# 24V_Converter.net
KiCad netlist of a schematic drawn in Altium Designer
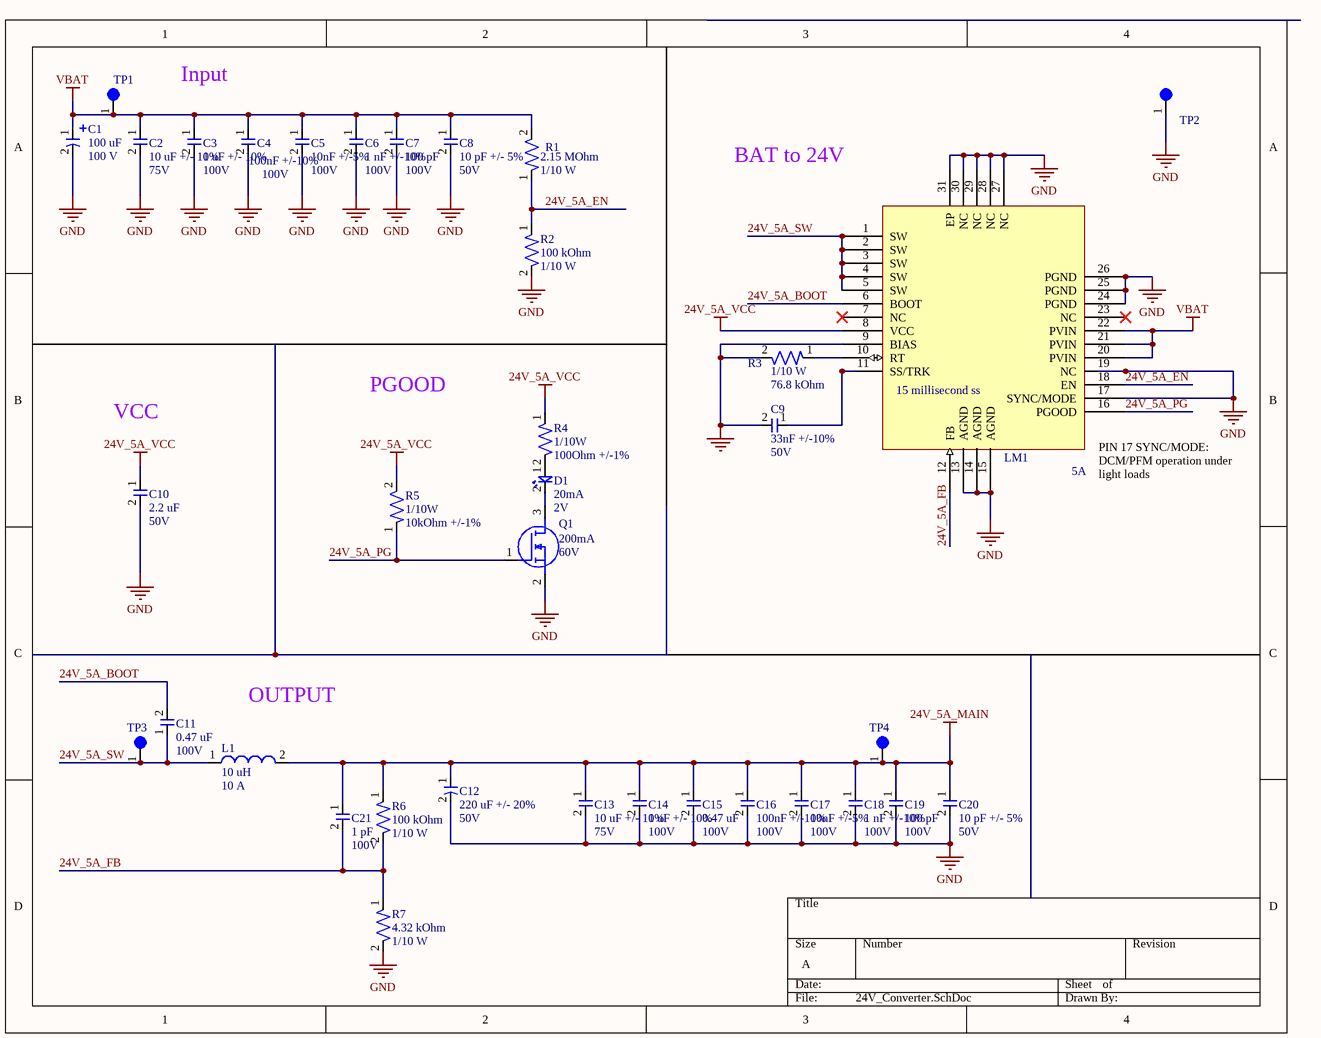
[diagram p0: 24V_Converter.SchDoc]

(export (version "E")
  (design (tool "Eeschema 10.0.6"))
  (components
    (comp (ref "C1")
      (value "100SEV100M12.5X16")
      (footprint "ELEC-100U-0001")
      (description "100 µF 100 V Aluminum Electrolytic Capacitors Radial, Can - SMD 2000 Hrs @ 85°C")
      (fields
        (field (name "MANUFACTURER") "Rubycon")
        (field (name "TOLERANCE") "+/- 20%")
        (field (name "CAPACITANCE") "100 uF")
        (field (name "VOLTAGE") "100 V")
      )
      (libsource (lib "MasterLib") (part "ELEC-100U-0001"))
    )
    (comp (ref "C2")
      (value "C3225X7R1N106K250AC")
      (footprint "CAP-1210")
      (description "10 µF ±10% 75V Ceramic Capacitor X7R 1210 (3225 Metric)")
      (fields (field (name "CAPACITANCE") "10 uF +/- 10%") (field (name "VOLTAGE RATING") "75V"))
      (libsource (lib "MasterLib") (part "CAP-10U-0004"))
    )
    (comp (ref "C3")
      (value "CL31B105KCHNNNE")
      (footprint "CAP-1206 - duplicate")
      (description "1 µF ±10% 100V Ceramic Capacitor X7R 1206 (3216 Metric)")
      (fields (field (name "CAPACITANCE") "1 uF +/- 10%") (field (name "VOLTAGE") "100V"))
      (libsource (lib "MasterLib") (part "CAP-1U-0001"))
    )
    (comp (ref "C4")
      (value "CC0603KRX7R0BB104")
      (footprint "CAP-0603")
      (description "CAP CER 0.1UF 100V X7R 0603")
      (fields
        (field (name "MANUFACTURER") "YAGEO")
        (field (name "CAPACITANCE") "100nF +/-10%")
        (field (name "VOLTAGE RATING") "100V")
      )
      (libsource (lib "MasterLib") (part "CAP-100N-0001"))
    )
    (comp (ref "C5")
      (value "C1608C0G2A103J080AC")
      (footprint "CAP-0603")
      (description "CAP CER 10000PF 100V C0G 0603")
      (fields
        (field (name "MANUFACTURER") "TDK Corporation")
        (field (name "CAPACITANCE") "10nF +/-5%")
        (field (name "VOLTAGE RATING") "100V")
      )
      (libsource (lib "MasterLib") (part "CAP-10N-0002"))
    )
    (comp (ref "C6")
      (value "C0603Y102K1RAC7867")
      (footprint "CAP-0603")
      (description "1000 pF ±10% 100V Ceramic Capacitor X7R 0603 (1608 Metric)")
      (fields (field (name "CAPACITANCE") "1 nF +/-10%") (field (name "VOLTAGE") "100V"))
      (libsource (lib "MasterLib") (part "CAP-1N-0001"))
    )
    (comp (ref "C7")
      (value "0603N101J101CT")
      (footprint "CAP-0603")
      (description "100 pF ±5% 100V Ceramic Capacitor C0G, NP0 0603 (1608 Metric)")
      (fields
        (field (name "TOLERANCE") "+/-5%")
        (field (name "CAPACITANCE") "100 pF")
        (field (name "VOLTAGE") "100V")
      )
      (libsource (lib "MasterLib") (part "CAP-100P-0002"))
    )
    (comp (ref "C8")
      (value "0603N100J500CT")
      (footprint "CAP-0603")
      (description "10 pF ±5% 50V Ceramic Capacitor C0G, NP0 0603 (1608 Metric)")
      (fields
        (field (name "MANUFACTURER") "Walshin Technology Corporation")
        (field (name "CAPACITANCE") "10 pF +/- 5%")
        (field (name "VOLTAGE RATING") "50V")
      )
      (libsource (lib "MasterLib") (part "CAP-10P-0001"))
    )
    (comp (ref "C9")
      (value "CC0603KRX7R9BB333")
      (footprint "CAP-0603")
      (description "0.033 µF ±10% 50V Ceramic Capacitor X7R 0603 (1608 Metric)")
      (fields
        (field (name "MANUFACTURER") "YAGEO")
        (field (name "CAPACITANCE") "33nF +/-10%")
        (field (name "VOLTAGE RATING") "50V")
      )
      (libsource (lib "MasterLib") (part "CAP-33N-0001"))
    )
    (comp (ref "C10")
      (value "UMK107BBJ225KA-T")
      (footprint "CAP-0603")
      (description "2.2 µF ±10% 50V Ceramic Capacitor X5R 0603 (1608 Metric)")
      (fields (field (name "CAPACITANCE") "2.2 uF") (field (name "OLTAGE") "50V"))
      (libsource (lib "MasterLib") (part "CAP-2.2U-0001"))
    )
    (comp (ref "C11")
      (value "KAM21KR72A474KL")
      (footprint "CAP-0805")
      (description "0.47 µF ±10% 100V Ceramic Capacitor X7R 0805 (2012 Metric)")
      (fields
        (field (name "TOLERANCE") "+/- 10%")
        (field (name "CAPACITANCE") "0.47 uF")
        (field (name "VOLTAGE") "100V")
      )
      (libsource (lib "MasterLib") (part "CAP-0.47U-0001"))
    )
    (comp (ref "C12")
      (value "50TZV220M10X10.5")
      (footprint "ELEC-220U-0003")
      (description "220 µF 50 V Aluminum Electrolytic Capacitors Radial, Can - SMD 2000 Hrs @ 105°C")
      (fields (field (name "CAPACITANCE") "220 uF +/- 20%") (field (name "VOLTAGE RATING") "50V"))
      (libsource (lib "MasterLib") (part "ELEC-220U-0003"))
    )
    (comp (ref "C13")
      (value "C3225X7R1N106K250AC")
      (footprint "CAP-1210")
      (description "10 µF ±10% 75V Ceramic Capacitor X7R 1210 (3225 Metric)")
      (fields (field (name "CAPACITANCE") "10 uF +/- 10%") (field (name "VOLTAGE RATING") "75V"))
      (libsource (lib "MasterLib") (part "CAP-10U-0004"))
    )
    (comp (ref "C14")
      (value "CL31B105KCHNNNE")
      (footprint "CAP-1206 - duplicate")
      (description "1 µF ±10% 100V Ceramic Capacitor X7R 1206 (3216 Metric)")
      (fields (field (name "CAPACITANCE") "1 uF +/- 10%") (field (name "VOLTAGE") "100V"))
      (libsource (lib "MasterLib") (part "CAP-1U-0001"))
    )
    (comp (ref "C15")
      (value "KAM21KR72A474KL")
      (footprint "CAP-0805")
      (description "0.47 µF ±10% 100V Ceramic Capacitor X7R 0805 (2012 Metric)")
      (fields
        (field (name "TOLERANCE") "+/- 10%")
        (field (name "CAPACITANCE") "0.47 uF")
        (field (name "VOLTAGE") "100V")
      )
      (libsource (lib "MasterLib") (part "CAP-0.47U-0001"))
    )
    (comp (ref "C16")
      (value "CC0603KRX7R0BB104")
      (footprint "CAP-0603")
      (description "CAP CER 0.1UF 100V X7R 0603")
      (fields
        (field (name "MANUFACTURER") "YAGEO")
        (field (name "CAPACITANCE") "100nF +/-10%")
        (field (name "VOLTAGE RATING") "100V")
      )
      (libsource (lib "MasterLib") (part "CAP-100N-0001"))
    )
    (comp (ref "C17")
      (value "C1608C0G2A103J080AC")
      (footprint "CAP-0603")
      (description "CAP CER 10000PF 100V C0G 0603")
      (fields
        (field (name "MANUFACTURER") "TDK Corporation")
        (field (name "CAPACITANCE") "10nF +/-5%")
        (field (name "VOLTAGE RATING") "100V")
      )
      (libsource (lib "MasterLib") (part "CAP-10N-0002"))
    )
    (comp (ref "C18")
      (value "C0603Y102K1RAC7867")
      (footprint "CAP-0603")
      (description "1000 pF ±10% 100V Ceramic Capacitor X7R 0603 (1608 Metric)")
      (fields (field (name "CAPACITANCE") "1 nF +/-10%") (field (name "VOLTAGE") "100V"))
      (libsource (lib "MasterLib") (part "CAP-1N-0001"))
    )
    (comp (ref "C19")
      (value "0603N101J101CT")
      (footprint "CAP-0603")
      (description "100 pF ±5% 100V Ceramic Capacitor C0G, NP0 0603 (1608 Metric)")
      (fields
        (field (name "TOLERANCE") "+/-5%")
        (field (name "CAPACITANCE") "100 pF")
        (field (name "VOLTAGE") "100V")
      )
      (libsource (lib "MasterLib") (part "CAP-100P-0002"))
    )
    (comp (ref "C20")
      (value "0603N100J500CT")
      (footprint "CAP-0603")
      (description "10 pF ±5% 50V Ceramic Capacitor C0G, NP0 0603 (1608 Metric)")
      (fields
        (field (name "MANUFACTURER") "Walshin Technology Corporation")
        (field (name "CAPACITANCE") "10 pF +/- 5%")
        (field (name "VOLTAGE RATING") "50V")
      )
      (libsource (lib "MasterLib") (part "CAP-10P-0001"))
    )
    (comp (ref "C21")
      (value "885012006087")
      (footprint "CAP-0603")
      (description "1 pF ±0.25pF 100V Ceramic Capacitor C0G, NP0 0603 (1608 Metric)")
      (fields
        (field (name "TOLERANCE") "+/- 0.25 pF")
        (field (name "CAPACITANCE") "1 pF")
        (field (name "VOLTAGE") "100V")
      )
      (libsource (lib "MasterLib") (part "CAP-1P-0001"))
    )
    (comp (ref "D1")
      (value "150060AS75000")
      (footprint "LED-0603")
      (description "CAP CER 0.1UF 100V X7R 0603")
      (fields
        (field (name "MANUFACTURER") "Wurth Electronik")
        (field (name "CURRENT RATING") "20mA")
        (field (name "VF") "2V")
      )
      (libsource (lib "MasterLib") (part "LED_Amber_0001"))
    )
    (comp (ref "L1")
      (value "SRP1270-100M")
      (footprint "PWRIND-10U-0002")
      (description "10 µH Shielded Drum Core, Wirewound Inductor 10 A 16.8mOhm Max Nonstandard")
      (fields
        (field (name "TOLERANCE") "+/- 20%")
        (field (name "INDUCTANCE") "10 uH")
        (field (name "DCI") "10 A")
      )
      (libsource (lib "MasterLib") (part "PWRIND-10U-0002"))
    )
    (comp (ref "LM1")
      (value "LM76005RNPR")
      (footprint "IC-30-WQFN(6x4)")
      (description "Buck Switching Regulator IC Positive Adjustable 1V 1 Output 5A 30-WFQFN Exposed Pad")
      (fields (field (name "MANUFACTURER") "Texas Instruments") (field (name "CURRENT") "5A"))
      (libsource (lib "MasterLib") (part "IC-BUCK-0006"))
    )
    (comp (ref "Q1")
      (value "T2N7002AK,LM")
      (footprint "NMOS-SOT23-3")
      (description "MOSFET N-CH 60V 200MA SOT23")
      (fields
        (field (name "MANUFACTURER") "Toshiba")
        (field (name "ID-CONTINUOUS") "200mA")
        (field (name "VDS-MAX") "60V")
      )
      (libsource (lib "MasterLib") (part "NMOS-200MA-0001"))
    )
    (comp (ref "R1")
      (value "RC0603FR-072M15L")
      (footprint "RES-0603")
      (description "2.15 MOhms ±1% 0.1W, 1/10W Chip Resistor 0603 (1608 Metric) Moisture Resistant Thick Film")
      (fields
        (field (name "TOLERANCE") "+/-1%")
        (field (name "RESISTANCE") "2.15 MOhm")
        (field (name "POWER") "1/10 W")
      )
      (libsource (lib "MasterLib") (part "RES-2.15M-0001"))
    )
    (comp (ref "R2")
      (value "RC0603FR-07100KL")
      (footprint "RES-0603")
      (description "100 kOhms ±1% 0.1W, 1/10W Chip Resistor 0603 (1608 Metric) Moisture Resistant Thick Film")
      (fields
        (field (name "TOLERANCE") "+/- 1%")
        (field (name "RESISTANCE") "100 kOhm")
        (field (name "POWER") "1/10 W")
      )
      (libsource (lib "MasterLib") (part "RES-100K-0003"))
    )
    (comp (ref "R3")
      (value "RC0603FR-0776K8L")
      (footprint "RES-0603")
      (description "76.8 kOhms ±1% 0.1W, 1/10W Chip Resistor 0603 (1608 Metric) Moisture Resistant Thick Film")
      (fields
        (field (name "MANUFACTURER") "Yageo")
        (field (name "TOLERANCE") "+/- 1%")
        (field (name "POWER") "1/10 W")
        (field (name "RESISTANCE") "76.8 kOhm")
      )
      (libsource (lib "MasterLib") (part "RES-76.8K-0001"))
    )
    (comp (ref "R4")
      (value "AC0603FR-10100RL")
      (footprint "RES-0603")
      (description "100 Ohms ±1% 0.1W, 1/10W Chip Resistor 0603 (1608 Metric) Automotive AEC-Q200 Thick Film")
      (fields
        (field (name "MANUFACTURER") "YAGEO")
        (field (name "POWER RATING") "1/10W")
        (field (name "RESISTANCE") "100Ohm +/-1%")
      )
      (libsource (lib "MasterLib") (part "RES-100-0002"))
    )
    (comp (ref "R5")
      (value "RC0603FR-0710KP")
      (footprint "RES-0603")
      (description "RES SMD 10K OHM 1% 1/10W 0603")
      (fields
        (field (name "MANUFACTURER") "YAGEO")
        (field (name "POWER RATING") "1/10W")
        (field (name "RESISTANCE") "10kOhm +/-1%")
      )
      (libsource (lib "MasterLib") (part "RES-10K-0002"))
    )
    (comp (ref "R6")
      (value "RC0603FR-07100KL")
      (footprint "RES-0603")
      (description "100 kOhms ±1% 0.1W, 1/10W Chip Resistor 0603 (1608 Metric) Moisture Resistant Thick Film")
      (fields
        (field (name "TOLERANCE") "+/- 1%")
        (field (name "RESISTANCE") "100 kOhm")
        (field (name "POWER") "1/10 W")
      )
      (libsource (lib "MasterLib") (part "RES-100K-0003"))
    )
    (comp (ref "R7")
      (value "RC0603FR-074K32L")
      (footprint "RES-0603")
      (description "4.32 kOhms ±1% 0.1W, 1/10W Chip Resistor 0603 (1608 Metric) Moisture Resistant Thick Film")
      (fields
        (field (name "TOLERANCE") "+/-1%")
        (field (name "RESISTANCE") "4.32 kOhm")
        (field (name "POWER") "1/10 W")
      )
      (libsource (lib "MasterLib") (part "RES-4.32K-0001"))
    )
    (comp (ref "TP1")
      (value "5003")
      (footprint "TEST-POINT-0001")
      (description "Oranange PC Test Point, Miniature Phoisphor Bronze Silver Plating Through Hole Mounting Type")
      (libsource (lib "MasterLib") (part "TEST-POINT-0001"))
    )
    (comp (ref "TP2")
      (value "5003")
      (footprint "TEST-POINT-0001")
      (description "Oranange PC Test Point, Miniature Phoisphor Bronze Silver Plating Through Hole Mounting Type")
      (libsource (lib "MasterLib") (part "TEST-POINT-0001"))
    )
    (comp (ref "TP3")
      (value "5003")
      (footprint "TEST-POINT-0001")
      (description "Oranange PC Test Point, Miniature Phoisphor Bronze Silver Plating Through Hole Mounting Type")
      (libsource (lib "MasterLib") (part "TEST-POINT-0001"))
    )
    (comp (ref "TP4")
      (value "5003")
      (footprint "TEST-POINT-0001")
      (description "Oranange PC Test Point, Miniature Phoisphor Bronze Silver Plating Through Hole Mounting Type")
      (libsource (lib "MasterLib") (part "TEST-POINT-0001"))
    )
  )
  (nets
    (net (code "1") (name "/24V_5A_BOOT") (class "Default")
      (node (ref "C11") (pin "2") (pinfunction "2_2") (pintype "passive"))
      (node (ref "LM1") (pin "6") (pinfunction "BOOT_6") (pintype "power_in"))
    )
    (net (code "2") (name "/24V_5A_EN") (class "Default")
      (node (ref "LM1") (pin "18") (pinfunction "EN_18") (pintype "power_in"))
      (node (ref "R1") (pin "1") (pinfunction "1_1") (pintype "passive"))
      (node (ref "R2") (pin "1") (pinfunction "1_1") (pintype "passive"))
    )
    (net (code "3") (name "/24V_5A_FB") (class "Default")
      (node (ref "C21") (pin "2") (pinfunction "2_2") (pintype "passive"))
      (node (ref "LM1") (pin "12") (pinfunction "FB_12") (pintype "input"))
      (node (ref "R6") (pin "2") (pinfunction "2_2") (pintype "passive"))
      (node (ref "R7") (pin "1") (pinfunction "1_1") (pintype "passive"))
    )
    (net (code "4") (name "/24V_5A_PG") (class "Default")
      (node (ref "LM1") (pin "16") (pinfunction "PGOOD_16") (pintype "power_in"))
      (node (ref "Q1") (pin "1") (pinfunction "G_1") (pintype "passive"))
      (node (ref "R5") (pin "1") (pinfunction "1_1") (pintype "passive"))
    )
    (net (code "5") (name "/24V_5A_SW") (class "Default")
      (node (ref "C11") (pin "1") (pinfunction "1_1") (pintype "passive"))
      (node (ref "L1") (pin "1") (pinfunction "1_1") (pintype "passive"))
      (node (ref "LM1") (pin "1") (pinfunction "SW_1") (pintype "power_in"))
      (node (ref "LM1") (pin "2") (pinfunction "SW_2") (pintype "power_in"))
      (node (ref "LM1") (pin "3") (pinfunction "SW_3") (pintype "power_in"))
      (node (ref "LM1") (pin "4") (pinfunction "SW_4") (pintype "power_in"))
      (node (ref "LM1") (pin "5") (pinfunction "SW_5") (pintype "power_in"))
      (node (ref "TP3") (pin "1") (pinfunction "0_1") (pintype "passive"))
    )
    (net (code "6") (name "24V_5A_MAIN") (class "Default")
      (node (ref "C12") (pin "1") (pinfunction "1_1") (pintype "passive"))
      (node (ref "C13") (pin "1") (pinfunction "1_1") (pintype "passive"))
      (node (ref "C14") (pin "1") (pinfunction "1_1") (pintype "passive"))
      (node (ref "C15") (pin "1") (pinfunction "1_1") (pintype "passive"))
      (node (ref "C16") (pin "1") (pinfunction "1_1") (pintype "passive"))
      (node (ref "C17") (pin "1") (pinfunction "1_1") (pintype "passive"))
      (node (ref "C18") (pin "1") (pinfunction "1_1") (pintype "passive"))
      (node (ref "C19") (pin "1") (pinfunction "1_1") (pintype "passive"))
      (node (ref "C20") (pin "1") (pinfunction "1_1") (pintype "passive"))
      (node (ref "C21") (pin "1") (pinfunction "1_1") (pintype "passive"))
      (node (ref "L1") (pin "2") (pinfunction "2_2") (pintype "passive"))
      (node (ref "R6") (pin "1") (pinfunction "1_1") (pintype "passive"))
      (node (ref "TP4") (pin "1") (pinfunction "0_1") (pintype "passive"))
    )
    (net (code "7") (name "24V_5A_VCC") (class "Default")
      (node (ref "C10") (pin "1") (pinfunction "1_1") (pintype "passive"))
      (node (ref "LM1") (pin "8") (pinfunction "VCC_8") (pintype "power_in"))
      (node (ref "R4") (pin "1") (pinfunction "1_1") (pintype "passive"))
      (node (ref "R5") (pin "2") (pinfunction "2_2") (pintype "passive"))
    )
    (net (code "8") (name "<NO NET>") (class "Default")
      (node (ref "C9") (pin "2") (pinfunction "2_2") (pintype "passive"))
      (node (ref "LM1") (pin "9") (pinfunction "BIAS_9") (pintype "power_in"))
      (node (ref "R3") (pin "2") (pinfunction "2_2") (pintype "passive"))
    )
    (net (code "9") (name "GND") (class "Default")
      (node (ref "C1") (pin "2") (pinfunction "2_2") (pintype "passive"))
      (node (ref "C10") (pin "2") (pinfunction "2_2") (pintype "passive"))
      (node (ref "C12") (pin "2") (pinfunction "2_2") (pintype "passive"))
      (node (ref "C13") (pin "2") (pinfunction "2_2") (pintype "passive"))
      (node (ref "C14") (pin "2") (pinfunction "2_2") (pintype "passive"))
      (node (ref "C15") (pin "2") (pinfunction "2_2") (pintype "passive"))
      (node (ref "C16") (pin "2") (pinfunction "2_2") (pintype "passive"))
      (node (ref "C17") (pin "2") (pinfunction "2_2") (pintype "passive"))
      (node (ref "C18") (pin "2") (pinfunction "2_2") (pintype "passive"))
      (node (ref "C19") (pin "2") (pinfunction "2_2") (pintype "passive"))
      (node (ref "C2") (pin "2") (pinfunction "2_2") (pintype "passive"))
      (node (ref "C20") (pin "2") (pinfunction "2_2") (pintype "passive"))
      (node (ref "C3") (pin "2") (pinfunction "2_2") (pintype "passive"))
      (node (ref "C4") (pin "2") (pinfunction "2_2") (pintype "passive"))
      (node (ref "C5") (pin "2") (pinfunction "2_2") (pintype "passive"))
      (node (ref "C6") (pin "2") (pinfunction "2_2") (pintype "passive"))
      (node (ref "C7") (pin "2") (pinfunction "2_2") (pintype "passive"))
      (node (ref "C8") (pin "2") (pinfunction "2_2") (pintype "passive"))
      (node (ref "LM1") (pin "13") (pinfunction "AGND_13") (pintype "power_in"))
      (node (ref "LM1") (pin "14") (pinfunction "AGND_14") (pintype "power_in"))
      (node (ref "LM1") (pin "15") (pinfunction "AGND_15") (pintype "power_in"))
      (node (ref "LM1") (pin "17") (pinfunction "SYNC/MODE_17") (pintype "power_in"))
      (node (ref "LM1") (pin "19") (pinfunction "NC_19") (pintype "power_in"))
      (node (ref "LM1") (pin "24") (pinfunction "PGND_24") (pintype "power_in"))
      (node (ref "LM1") (pin "25") (pinfunction "PGND_25") (pintype "power_in"))
      (node (ref "LM1") (pin "26") (pinfunction "PGND_26") (pintype "power_in"))
      (node (ref "LM1") (pin "27") (pinfunction "NC_27") (pintype "power_in"))
      (node (ref "LM1") (pin "28") (pinfunction "NC_28") (pintype "power_in"))
      (node (ref "LM1") (pin "29") (pinfunction "NC_29") (pintype "power_in"))
      (node (ref "LM1") (pin "30") (pinfunction "NC_30") (pintype "power_in"))
      (node (ref "LM1") (pin "31") (pinfunction "EP_31") (pintype "power_in"))
      (node (ref "Q1") (pin "2") (pinfunction "S_2") (pintype "passive"))
      (node (ref "R2") (pin "2") (pinfunction "2_2") (pintype "passive"))
      (node (ref "R7") (pin "2") (pinfunction "2_2") (pintype "passive"))
      (node (ref "TP2") (pin "1") (pinfunction "0_1") (pintype "passive"))
    )
    (net (code "10") (name "Net-(D1-Pad1)") (class "Default")
      (node (ref "D1") (pin "1") (pinfunction "1_1") (pintype "passive"))
      (node (ref "R4") (pin "2") (pinfunction "2_2") (pintype "passive"))
    )
    (net (code "11") (name "Net-(LM1-RT)") (class "Default")
      (node (ref "LM1") (pin "10") (pinfunction "RT_10") (pintype "bidirectional"))
      (node (ref "R3") (pin "1") (pinfunction "1_1") (pintype "passive"))
    )
    (net (code "12") (name "Net-(LM1-SS{slash}TRK)") (class "Default")
      (node (ref "C9") (pin "1") (pinfunction "1_1") (pintype "passive"))
      (node (ref "LM1") (pin "11") (pinfunction "SS/TRK_11") (pintype "passive"))
    )
    (net (code "13") (name "Net-(Q1-D)") (class "Default")
      (node (ref "D1") (pin "2") (pinfunction "2_2") (pintype "passive"))
      (node (ref "Q1") (pin "3") (pinfunction "D_3") (pintype "passive"))
    )
    (net (code "14") (name "VBAT") (class "Default")
      (node (ref "C1") (pin "1") (pinfunction "1_1") (pintype "passive"))
      (node (ref "C2") (pin "1") (pinfunction "1_1") (pintype "passive"))
      (node (ref "C3") (pin "1") (pinfunction "1_1") (pintype "passive"))
      (node (ref "C4") (pin "1") (pinfunction "1_1") (pintype "passive"))
      (node (ref "C5") (pin "1") (pinfunction "1_1") (pintype "passive"))
      (node (ref "C6") (pin "1") (pinfunction "1_1") (pintype "passive"))
      (node (ref "C7") (pin "1") (pinfunction "1_1") (pintype "passive"))
      (node (ref "C8") (pin "1") (pinfunction "1_1") (pintype "passive"))
      (node (ref "LM1") (pin "20") (pinfunction "PVIN_20") (pintype "power_in"))
      (node (ref "LM1") (pin "21") (pinfunction "PVIN_21") (pintype "power_in"))
      (node (ref "LM1") (pin "22") (pinfunction "PVIN_22") (pintype "power_in"))
      (node (ref "R1") (pin "2") (pinfunction "2_2") (pintype "passive"))
      (node (ref "TP1") (pin "1") (pinfunction "0_1") (pintype "passive"))
    )
    (net (code "15") (name "unconnected-(LM1-NC-Pad7)") (class "Default")
      (node (ref "LM1") (pin "7") (pinfunction "NC_7") (pintype "power_in+no_connect"))
    )
    (net (code "16") (name "unconnected-(LM1-NC-Pad23)") (class "Default")
      (node (ref "LM1") (pin "23") (pinfunction "NC_23") (pintype "tri_state+no_connect"))
    )
  )
)
